# Relay_Control.net
KiCad netlist of a schematic drawn in Altium Designer
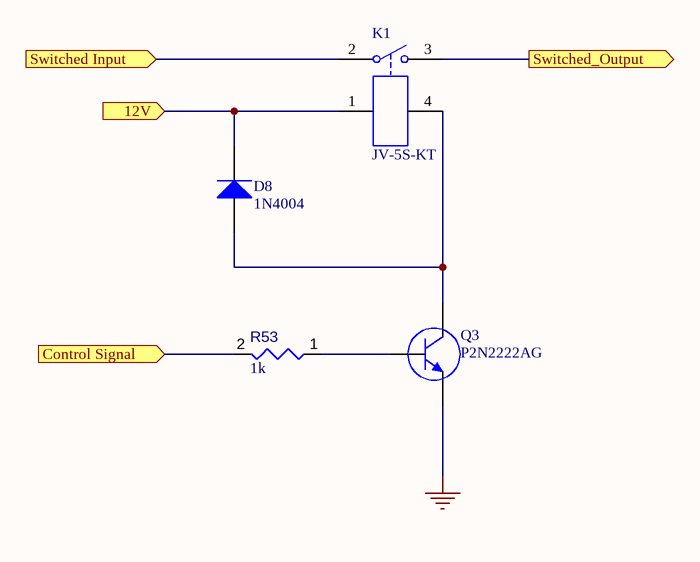
[diagram p0: Relay Control.SchDoc]

(export (version "E")
  (design (tool "Eeschema 10.0.6"))
  (components
    (comp (ref "D8")
      (value "1N4004")
      (footprint "FAIR-DO-41-2")
      (fields (field (name "MANUFACTURER") "Fairchild Semiconductor"))
      (libsource (lib "University of Western Australia") (part "D-AK-2"))
    )
    (comp (ref "K1")
      (value "JV-5S-KT")
      (footprint "FJSU-JV-5S-KT_V")
      (description "Power Relay, 5 A, 125 Ohm, -40 to 70 degc, 4-Pin THD, RoHS")
      (fields (field (name "MANUFACTURER") "Fujitsu"))
      (libsource (lib "University of Western Australia") (part "RELAY-SPST-4-A"))
    )
    (comp (ref "Q3")
      (value "P2N2222AG")
      (footprint "ONSC-TO-92-3-29-11")
      (description "Small Signal Bipolar Transistor, 0.6A I(C), 40V V(BR)CEO, 1-Element, NPN, Silicon, TO-92")
      (libsource (lib "University of Western Australia") (part "TRANS-NPN-3"))
    )
    (comp (ref "R53")
      (value "1k")
      (footprint "RESA60-630X240")
      (description "Fixed Resistor, Metal Film, 0.25W, 1000ohm, 250V, 1% +/-Tol, 100ppm/Cel, Through Hole Mount")
      (fields (field (name "TOLERANCE") "1%") (field (name "POWER") "250mW"))
      (libsource (lib "University of Western Australia") (part "RES-2"))
    )
  )
  (nets
    (net (code "1") (name "/12V") (class "Default")
      (node (ref "D8") (pin "2") (pinfunction "K_2") (pintype "passive"))
      (node (ref "K1") (pin "1") (pinfunction "1_1") (pintype "passive"))
    )
    (net (code "2") (name "/Control Signal") (class "Default")
      (node (ref "R53") (pin "2") (pinfunction "2_2") (pintype "passive"))
    )
    (net (code "3") (name "/Switched Input") (class "Default")
      (node (ref "K1") (pin "2") (pinfunction "2_2") (pintype "passive"))
    )
    (net (code "4") (name "/Switched_Output") (class "Default")
      (node (ref "K1") (pin "3") (pinfunction "3_3") (pintype "passive"))
    )
    (net (code "5") (name "GND") (class "Default")
      (node (ref "Q3") (pin "1") (pinfunction "E_1") (pintype "passive"))
    )
    (net (code "6") (name "Net-(D8-A)") (class "Default")
      (node (ref "D8") (pin "1") (pinfunction "A_1") (pintype "passive"))
      (node (ref "K1") (pin "4") (pinfunction "4_4") (pintype "passive"))
      (node (ref "Q3") (pin "3") (pinfunction "C_3") (pintype "passive"))
    )
    (net (code "7") (name "Net-(Q3-B)") (class "Default")
      (node (ref "Q3") (pin "2") (pinfunction "B_2") (pintype "passive"))
      (node (ref "R53") (pin "1") (pinfunction "1_1") (pintype "passive"))
    )
  )
)
